# SX126xMB2xAS_e588v01a.net
KiCad netlist of a schematic drawn in Altium Designer
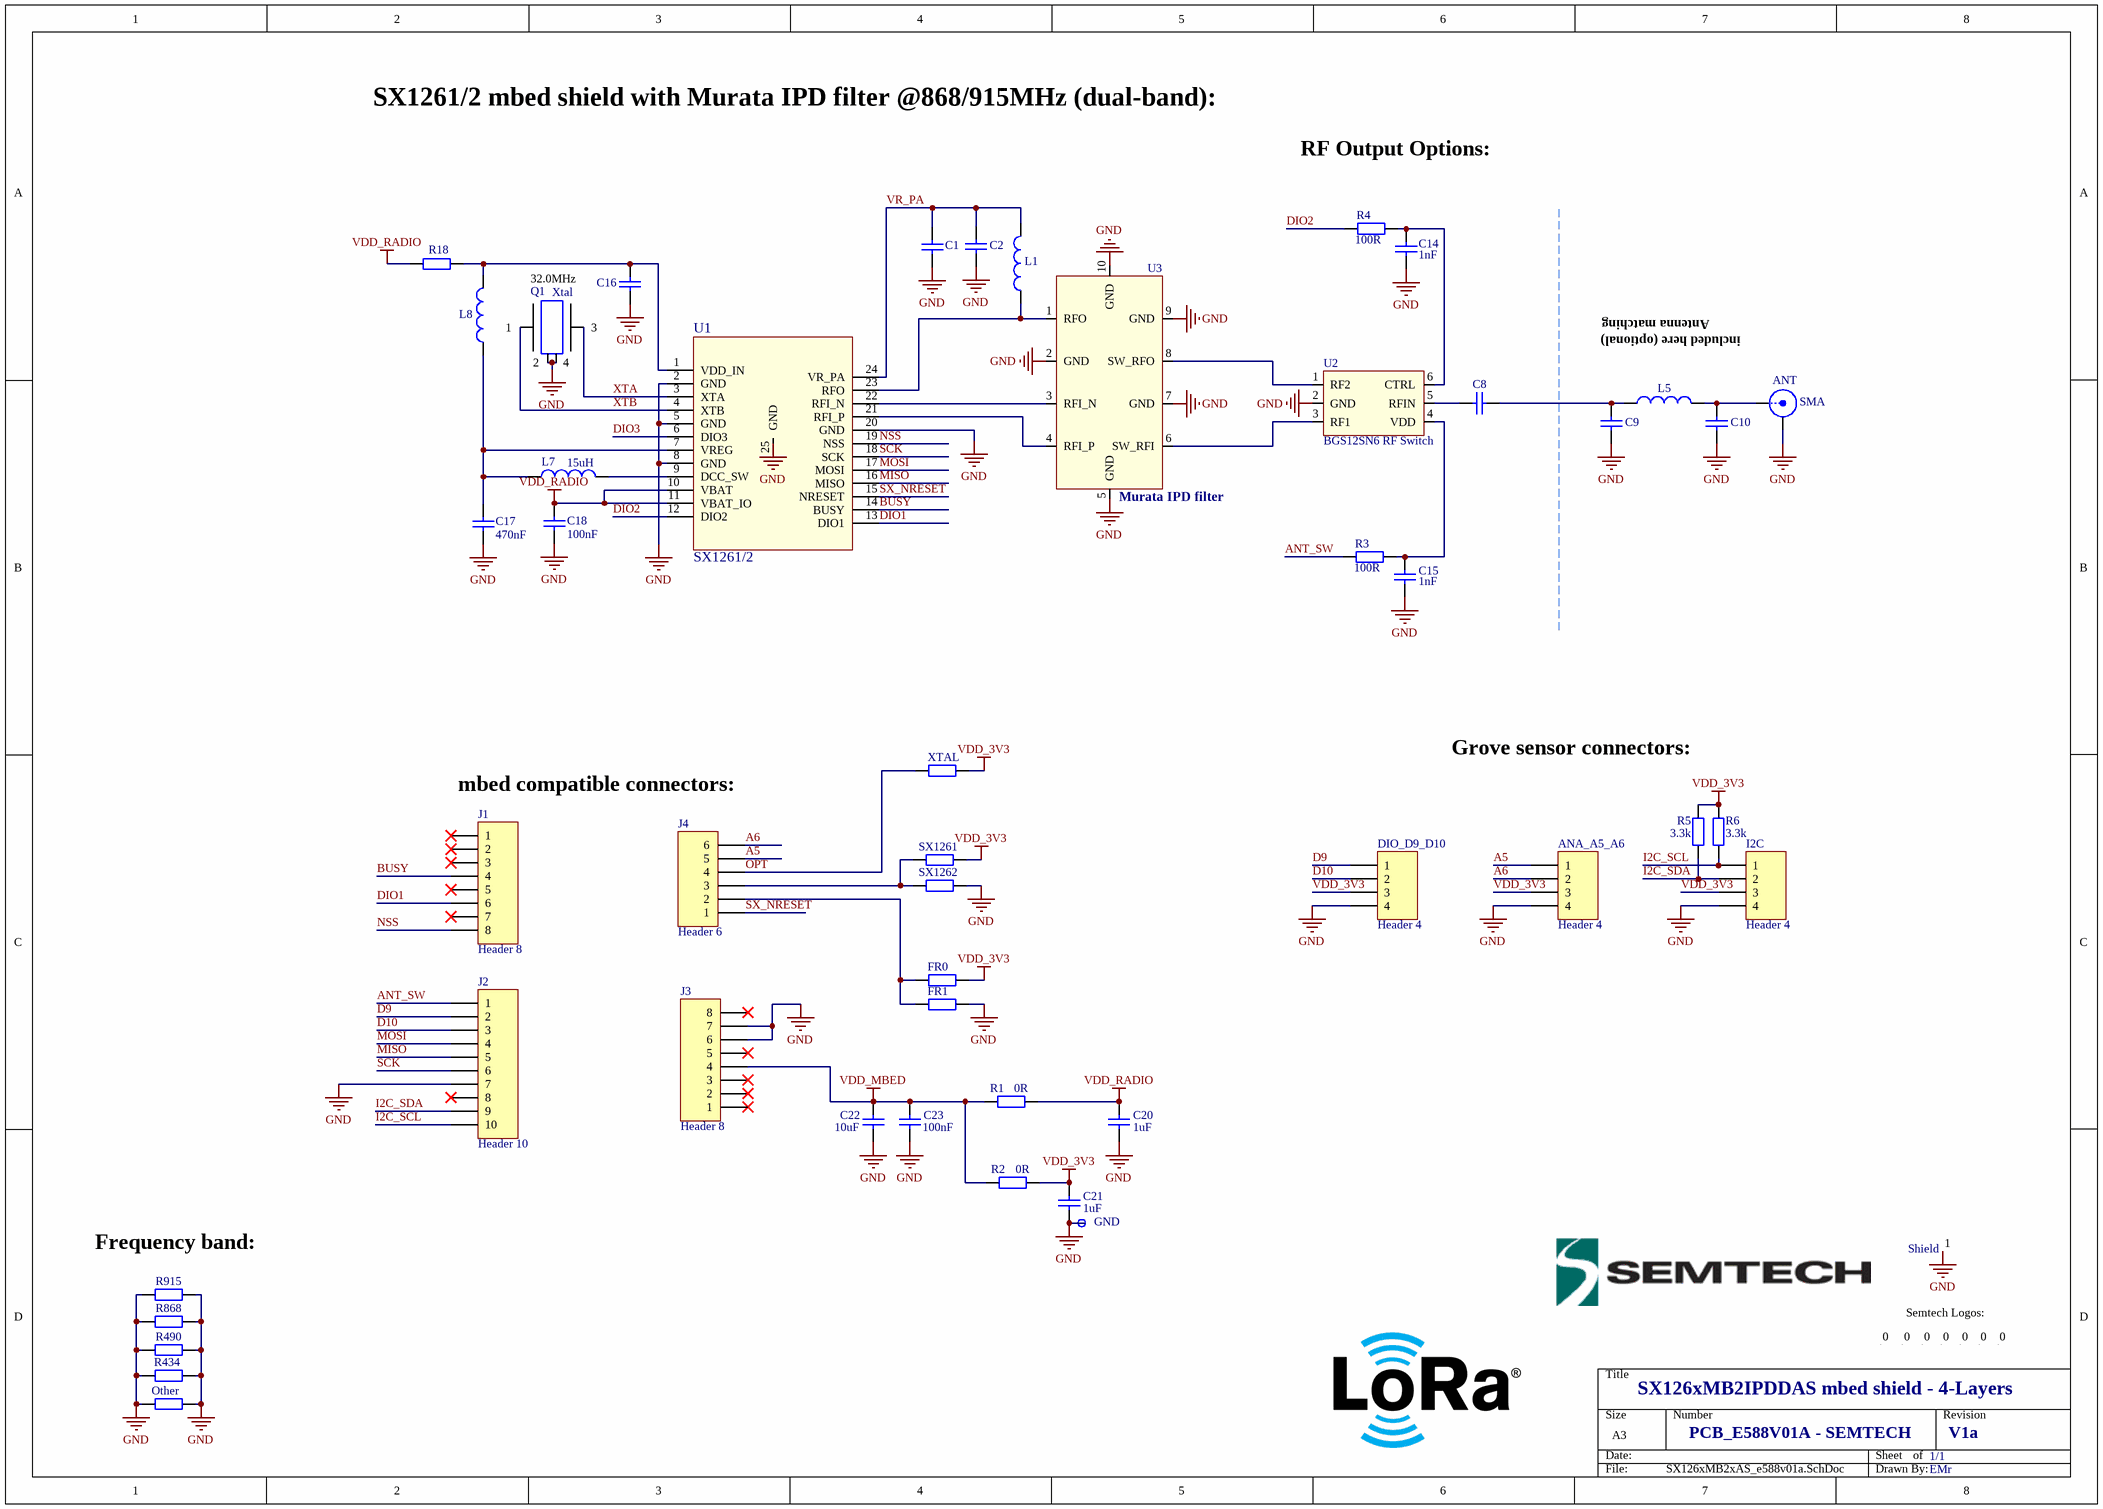
[diagram p0: SX126xMB2xAS_e588v01a.SchDoc]

(export (version "E")
  (design (tool "Eeschema 10.0.6"))
  (components
    (comp (ref "ANA_A5_A6")
      (value "Header 4")
      (footprint "1125S-4P_connector")
      (description "Header, 4-Pin")
      (fields (field (name "PUBLISHER") "Altium Limited"))
      (libsource (lib "SX126xMB2xAS_e588v01a") (part "Header 4"))
    )
    (comp (ref "ANT")
      (value "SMA")
      (footprint "SMA_end_launch_1.0mm_9.52mm")
      (description "SMA Straight Connector")
      (fields (field (name "PUBLISHER") "Altium Limited"))
      (libsource (lib "SX126xMB2xAS_e588v01a") (part "SMA"))
    )
    (comp (ref "C1")
      (value "Cap")
      (footprint "rlc_201_smd")
      (description "Capacitor SMD")
      (fields (field (name "PUBLISHER") "Altium Limited"))
      (libsource (lib "SX126xMB2xAS_e588v01a") (part "Cap"))
    )
    (comp (ref "C2")
      (value "Cap")
      (footprint "rlc_201_smd")
      (description "Capacitor SMD")
      (fields (field (name "PUBLISHER") "Altium Limited"))
      (libsource (lib "SX126xMB2xAS_e588v01a") (part "Cap"))
    )
    (comp (ref "C8")
      (value "Cap")
      (footprint "rlc_201_smd")
      (description "Capacitor SMD")
      (fields (field (name "PUBLISHER") "Altium Limited"))
      (libsource (lib "SX126xMB2xAS_e588v01a") (part "Cap"))
    )
    (comp (ref "C9")
      (value "Cap")
      (footprint "rlc_201_smd")
      (description "Capacitor SMD")
      (fields (field (name "PUBLISHER") "Altium Limited"))
      (libsource (lib "SX126xMB2xAS_e588v01a") (part "Cap"))
    )
    (comp (ref "C10")
      (value "Cap")
      (footprint "rlc_201_smd")
      (description "Capacitor SMD")
      (fields (field (name "PUBLISHER") "Altium Limited"))
      (libsource (lib "SX126xMB2xAS_e588v01a") (part "Cap"))
    )
    (comp (ref "C14")
      (value "1nF")
      (footprint "rlc_201_smd")
      (description "Capacitor SMD")
      (fields (field (name "Comment") "Cap") (field (name "PUBLISHER") "Altium Limited"))
      (libsource (lib "SX126xMB2xAS_e588v01a") (part "Cap"))
    )
    (comp (ref "C15")
      (value "1nF")
      (footprint "rlc_201_smd")
      (description "Capacitor SMD")
      (fields (field (name "Comment") "Cap") (field (name "PUBLISHER") "Altium Limited"))
      (libsource (lib "SX126xMB2xAS_e588v01a") (part "Cap"))
    )
    (comp (ref "C16")
      (value "Cap")
      (footprint "rlc_402_smd_small")
      (description "Capacitor SMD")
      (fields (field (name "PUBLISHER") "Altium Limited"))
      (libsource (lib "SX126xMB2xAS_e588v01a") (part "Cap"))
    )
    (comp (ref "C17")
      (value "470nF")
      (footprint "rlc_402_smd_small")
      (description "Capacitor SMD")
      (fields (field (name "Comment") "Cap") (field (name "PUBLISHER") "Altium Limited"))
      (libsource (lib "SX126xMB2xAS_e588v01a") (part "Cap"))
    )
    (comp (ref "C18")
      (value "100nF")
      (footprint "rlc_201_smd")
      (description "Capacitor SMD")
      (fields (field (name "Comment") "Cap") (field (name "PUBLISHER") "Altium Limited"))
      (libsource (lib "SX126xMB2xAS_e588v01a") (part "Cap"))
    )
    (comp (ref "C20")
      (value "1uF")
      (footprint "rlc_603_smd")
      (description "Capacitor SMD")
      (fields (field (name "Comment") "Cap") (field (name "PUBLISHER") "Altium Limited"))
      (libsource (lib "SX126xMB2xAS_e588v01a") (part "Cap"))
    )
    (comp (ref "C21")
      (value "1uF")
      (footprint "rlc_603_smd")
      (description "Capacitor SMD")
      (fields (field (name "Comment") "Cap") (field (name "PUBLISHER") "Altium Limited"))
      (libsource (lib "SX126xMB2xAS_e588v01a") (part "Cap"))
    )
    (comp (ref "C22")
      (value "10uF")
      (footprint "rlc_603_smd")
      (description "Capacitor SMD")
      (fields (field (name "Comment") "Cap") (field (name "PUBLISHER") "Altium Limited"))
      (libsource (lib "SX126xMB2xAS_e588v01a") (part "Cap"))
    )
    (comp (ref "C23")
      (value "100nF")
      (footprint "rlc_201_smd")
      (description "Capacitor SMD")
      (fields (field (name "Comment") "Cap") (field (name "PUBLISHER") "Altium Limited"))
      (libsource (lib "SX126xMB2xAS_e588v01a") (part "Cap"))
    )
    (comp (ref "DIO_D9_D10")
      (value "Header 4")
      (footprint "1125S-4P_connector")
      (description "Header, 4-Pin")
      (fields (field (name "PUBLISHER") "Altium Limited"))
      (libsource (lib "SX126xMB2xAS_e588v01a") (part "Header 4"))
    )
    (comp (ref "FR0")
      (value "Resistor")
      (footprint "rlc_402_smd")
      (description "Resistor SMD - IEC symbol version")
      (libsource (lib "") (part "Resistor_1"))
    )
    (comp (ref "FR1")
      (value "Resistor")
      (footprint "rlc_402_smd")
      (description "Resistor SMD - IEC symbol version")
      (libsource (lib "") (part "Resistor_1"))
    )
    (comp (ref "GND")
      (value "Test Pin")
      (footprint "pin_0.9mm")
      (libsource (lib "SX126xMB2xAS_e588v01a") (part "test_pin"))
    )
    (comp (ref "I2C")
      (value "Header 4")
      (footprint "1125S-4P_connector")
      (description "Header, 4-Pin")
      (fields (field (name "PUBLISHER") "Altium Limited"))
      (libsource (lib "SX126xMB2xAS_e588v01a") (part "Header 4"))
    )
    (comp (ref "J1")
      (value "Header 8")
      (footprint "HDR1X8")
      (description "Header, 8-Pin")
      (fields (field (name "PUBLISHER") "Altium Limited"))
      (libsource (lib "SX126xMB2xAS_e588v01a") (part "Header 8"))
    )
    (comp (ref "J2")
      (value "Header 10")
      (footprint "HDR1X10")
      (description "Header, 10-Pin")
      (fields (field (name "PUBLISHER") "Altium Limited"))
      (libsource (lib "SX126xMB2xAS_e588v01a") (part "Header 10"))
    )
    (comp (ref "J3")
      (value "Header 8")
      (footprint "HDR1X8")
      (description "Header, 8-Pin")
      (fields (field (name "PUBLISHER") "Altium Limited"))
      (libsource (lib "") (part "Header 8_1"))
    )
    (comp (ref "J4")
      (value "Header 6")
      (footprint "HDR1X6")
      (description "Header, 6-Pin")
      (fields (field (name "PUBLISHER") "Altium Limited"))
      (libsource (lib "SX126xMB2xAS_e588v01a") (part "Header 6"))
    )
    (comp (ref "L1")
      (value "Inductor")
      (footprint "rlc_402_smd_small")
      (description "Inductor SMD")
      (fields (field (name "PUBLISHER") "Altium Limited"))
      (libsource (lib "") (part "Inductor_1"))
    )
    (comp (ref "L5")
      (value "Inductor")
      (footprint "rlc_201_smd")
      (description "Inductor SMD")
      (fields (field (name "PUBLISHER") "Altium Limited"))
      (libsource (lib "") (part "Inductor_1"))
    )
    (comp (ref "L7")
      (value "15uH")
      (footprint "rlc_805_smd_small")
      (description "Inductor SMD")
      (fields (field (name "Comment") "Inductor") (field (name "PUBLISHER") "Altium Limited"))
      (libsource (lib "") (part "Inductor_1"))
    )
    (comp (ref "L8")
      (value "Inductor")
      (footprint "rlc_402_smd_small")
      (description "Inductor SMD")
      (fields (field (name "PUBLISHER") "Altium Limited"))
      (libsource (lib "SX126xMB2xAS_e588v01a") (part "Inductor"))
    )
    (comp (ref "Logo Bot1")
      (value "Logo symbol")
      (footprint "Logo LoRa Size4")
      (description "Schematic symbol for Logo")
      (libsource (lib "SX126xMB2xAS_e588v01a") (part "Logo"))
    )
    (comp (ref "Logo ESD1")
      (value "Logo symbol")
      (footprint "Logo ESD")
      (description "Schematic symbol for Logo")
      (libsource (lib "SX126xMB2xAS_e588v01a") (part "Logo"))
    )
    (comp (ref "Logo Recycling1")
      (value "Logo symbol")
      (footprint "Logo Recycling1")
      (description "Schematic symbol for Logo")
      (libsource (lib "SX126xMB2xAS_e588v01a") (part "Logo"))
    )
    (comp (ref "Logo Semtech_1")
      (value "Logo symbol")
      (footprint "logo_semtech_horiz_size3")
      (description "Schematic symbol for Logo")
      (libsource (lib "SX126xMB2xAS_e588v01a") (part "Logo"))
    )
    (comp (ref "Logo_LoRA_Top1")
      (value "Logo symbol")
      (footprint "Logo LoRa Size4")
      (description "Schematic symbol for Logo")
      (libsource (lib "SX126xMB2xAS_e588v01a") (part "Logo"))
    )
    (comp (ref "Logo_mbed1")
      (value "Logo symbol")
      (footprint "logo mbed 2")
      (description "Schematic symbol for Logo")
      (libsource (lib "SX126xMB2xAS_e588v01a") (part "Logo"))
    )
    (comp (ref "Logo_Semtech1")
      (value "Logo symbol")
      (footprint "logo_semtech_horiz_size4")
      (description "Schematic symbol for Logo")
      (libsource (lib "SX126xMB2xAS_e588v01a") (part "Logo"))
    )
    (comp (ref "Other")
      (value "Resistor")
      (footprint "rlc_402_smd")
      (description "Resistor SMD - IEC symbol version")
      (libsource (lib "SX126xMB2xAS_e588v01a") (part "Resistor"))
    )
    (comp (ref "Q1")
      (value "Xtal")
      (footprint "nd2016da")
      (description "Crystal with GND pins")
      (fields (field (name "ALTIUM_VALUE") "32.0MHz"))
      (libsource (lib "SX126xMB2xAS_e588v01a") (part "Xtal GND"))
    )
    (comp (ref "R1")
      (value "0R")
      (footprint "rlc_603_smd")
      (description "Resistor SMD - IEC symbol version")
      (fields (field (name "Comment") "Resistor"))
      (libsource (lib "SX126xMB2xAS_e588v01a") (part "Resistor"))
    )
    (comp (ref "R2")
      (value "0R")
      (footprint "rlc_603_smd")
      (description "Resistor SMD - IEC symbol version")
      (fields (field (name "Comment") "Resistor"))
      (libsource (lib "SX126xMB2xAS_e588v01a") (part "Resistor"))
    )
    (comp (ref "R3")
      (value "100R")
      (footprint "rlc_201_smd")
      (description "Resistor SMD - IEC symbol version")
      (fields (field (name "Comment") "Resistor"))
      (libsource (lib "SX126xMB2xAS_e588v01a") (part "Resistor"))
    )
    (comp (ref "R4")
      (value "100R")
      (footprint "rlc_201_smd")
      (description "Resistor SMD - IEC symbol version")
      (fields (field (name "Comment") "Resistor"))
      (libsource (lib "SX126xMB2xAS_e588v01a") (part "Resistor"))
    )
    (comp (ref "R5")
      (value "3.3k")
      (footprint "rlc_201_smd")
      (description "Resistor SMD - IEC symbol version")
      (fields (field (name "Comment") "Resistor"))
      (libsource (lib "") (part "Resistor_2"))
    )
    (comp (ref "R6")
      (value "3.3k")
      (footprint "rlc_201_smd")
      (description "Resistor SMD - IEC symbol version")
      (fields (field (name "Comment") "Resistor"))
      (libsource (lib "") (part "Resistor_2"))
    )
    (comp (ref "R18")
      (value "Resistor")
      (footprint "rlc_402_smd_small")
      (description "Resistor SMD - IEC symbol version")
      (libsource (lib "SX126xMB2xAS_e588v01a") (part "Resistor"))
    )
    (comp (ref "R434")
      (value "Resistor")
      (footprint "rlc_402_smd")
      (description "Resistor SMD - IEC symbol version")
      (libsource (lib "SX126xMB2xAS_e588v01a") (part "Resistor"))
    )
    (comp (ref "R490")
      (value "Resistor")
      (footprint "rlc_402_smd")
      (description "Resistor SMD - IEC symbol version")
      (libsource (lib "SX126xMB2xAS_e588v01a") (part "Resistor"))
    )
    (comp (ref "R868")
      (value "Resistor")
      (footprint "rlc_402_smd")
      (description "Resistor SMD - IEC symbol version")
      (libsource (lib "SX126xMB2xAS_e588v01a") (part "Resistor"))
    )
    (comp (ref "R915")
      (value "Resistor")
      (footprint "rlc_402_smd")
      (description "Resistor SMD - IEC symbol version")
      (libsource (lib "SX126xMB2xAS_e588v01a") (part "Resistor"))
    )
    (comp (ref "Shield")
      (value "Logo symbol")
      (footprint "BMIS-209-F - Shield")
      (description "Shield - EMI Gasket - Standard Surface Mount Shields")
      (libsource (lib "SX126xMB2xAS_e588v01a") (part "Shield"))
    )
    (comp (ref "SX1261")
      (value "Resistor")
      (footprint "rlc_402_smd")
      (description "Resistor SMD - IEC symbol version")
      (libsource (lib "") (part "Resistor_1"))
    )
    (comp (ref "SX1262")
      (value "Resistor")
      (footprint "rlc_402_smd")
      (description "Resistor SMD - IEC symbol version")
      (libsource (lib "") (part "Resistor_1"))
    )
    (comp (ref "U1")
      (value "SX1261/2")
      (footprint "vqfn24_4x4mm")
      (description "SX1262- Ultra low power RF transceiver")
      (libsource (lib "SX126xMB2xAS_e588v01a") (part "SX126x"))
    )
    (comp (ref "U2")
      (value "BGS12SN6 RF Switch")
      (footprint "TSNP-6-2")
      (description "BGS12SN6 Infineon RF Switch")
      (libsource (lib "SX126xMB2xAS_e588v01a") (part "BGS12SN6 RF Switch"))
    )
    (comp (ref "U3")
      (value "Murata IPD filter")
      (footprint "IPD Filter")
      (description "0900FM15D0039 - Johanson IPD Filter for SX1261, SX1262")
      (libsource (lib "SX126xMB2xAS_e588v01a") (part "IPD filter"))
    )
    (comp (ref "XTAL")
      (value "Resistor")
      (footprint "rlc_402_smd")
      (description "Resistor SMD - IEC symbol version")
      (libsource (lib "") (part "Resistor_1"))
    )
  )
  (nets
    (net (code "1") (name "/A5") (class "Default")
      (node (ref "ANA_A5_A6") (pin "1") (pinfunction "1_1") (pintype "passive"))
      (node (ref "J4") (pin "5") (pinfunction "5_5") (pintype "passive"))
    )
    (net (code "2") (name "/A6") (class "Default")
      (node (ref "ANA_A5_A6") (pin "2") (pinfunction "2_2") (pintype "passive"))
      (node (ref "J4") (pin "6") (pinfunction "6_6") (pintype "passive"))
    )
    (net (code "3") (name "/ANT_SW") (class "Default")
      (node (ref "J2") (pin "1") (pinfunction "1_1") (pintype "passive"))
      (node (ref "R3") (pin "2") (pinfunction "2_2") (pintype "passive"))
    )
    (net (code "4") (name "/BUSY") (class "Default")
      (node (ref "J1") (pin "4") (pinfunction "4_4") (pintype "passive"))
      (node (ref "U1") (pin "14") (pinfunction "BUSY_14") (pintype "passive"))
    )
    (net (code "5") (name "/D9") (class "Default")
      (node (ref "DIO_D9_D10") (pin "1") (pinfunction "1_1") (pintype "passive"))
      (node (ref "J2") (pin "2") (pinfunction "2_2") (pintype "passive"))
    )
    (net (code "6") (name "/D10") (class "Default")
      (node (ref "DIO_D9_D10") (pin "2") (pinfunction "2_2") (pintype "passive"))
      (node (ref "J2") (pin "3") (pinfunction "3_3") (pintype "passive"))
    )
    (net (code "7") (name "/DIO1") (class "Default")
      (node (ref "J1") (pin "6") (pinfunction "6_6") (pintype "passive"))
      (node (ref "U1") (pin "13") (pinfunction "DIO1_13") (pintype "passive"))
    )
    (net (code "8") (name "/DIO2") (class "Default")
      (node (ref "R4") (pin "2") (pinfunction "2_2") (pintype "passive"))
      (node (ref "U1") (pin "12") (pinfunction "DIO2_12") (pintype "passive"))
    )
    (net (code "9") (name "/DIO3") (class "Default")
      (node (ref "U1") (pin "6") (pinfunction "DIO3_6") (pintype "passive"))
    )
    (net (code "10") (name "/I2C_SCL") (class "Default")
      (node (ref "I2C") (pin "1") (pinfunction "1_1") (pintype "passive"))
      (node (ref "J2") (pin "10") (pinfunction "10_10") (pintype "passive"))
      (node (ref "R6") (pin "1") (pinfunction "1_1") (pintype "passive"))
    )
    (net (code "11") (name "/I2C_SDA") (class "Default")
      (node (ref "I2C") (pin "2") (pinfunction "2_2") (pintype "passive"))
      (node (ref "J2") (pin "9") (pinfunction "9_9") (pintype "passive"))
      (node (ref "R5") (pin "1") (pinfunction "1_1") (pintype "passive"))
    )
    (net (code "12") (name "/MISO") (class "Default")
      (node (ref "J2") (pin "5") (pinfunction "5_5") (pintype "passive"))
      (node (ref "U1") (pin "16") (pinfunction "MISO_16") (pintype "passive"))
    )
    (net (code "13") (name "/MOSI") (class "Default")
      (node (ref "J2") (pin "4") (pinfunction "4_4") (pintype "passive"))
      (node (ref "U1") (pin "17") (pinfunction "MOSI_17") (pintype "passive"))
    )
    (net (code "14") (name "/NSS") (class "Default")
      (node (ref "J1") (pin "8") (pinfunction "8_8") (pintype "passive"))
      (node (ref "U1") (pin "19") (pinfunction "NSS_19") (pintype "passive"))
    )
    (net (code "15") (name "/OPT") (class "Default")
      (node (ref "J4") (pin "4") (pinfunction "4_4") (pintype "passive"))
      (node (ref "XTAL") (pin "2") (pinfunction "2_2") (pintype "passive"))
    )
    (net (code "16") (name "/SCK") (class "Default")
      (node (ref "J2") (pin "6") (pinfunction "6_6") (pintype "passive"))
      (node (ref "U1") (pin "18") (pinfunction "SCK_18") (pintype "passive"))
    )
    (net (code "17") (name "/SX_NRESET") (class "Default")
      (node (ref "J4") (pin "1") (pinfunction "1_1") (pintype "passive"))
      (node (ref "U1") (pin "15") (pinfunction "NRESET_15") (pintype "passive"))
    )
    (net (code "18") (name "/VR_PA") (class "Default")
      (node (ref "C1") (pin "2") (pinfunction "2_2") (pintype "passive"))
      (node (ref "C2") (pin "2") (pinfunction "2_2") (pintype "passive"))
      (node (ref "L1") (pin "2") (pinfunction "2_2") (pintype "passive"))
      (node (ref "U1") (pin "24") (pinfunction "VR_PA_24") (pintype "power_in"))
    )
    (net (code "19") (name "/XTA") (class "Default")
      (node (ref "Q1") (pin "3") (pinfunction "3_3") (pintype "passive"))
      (node (ref "U1") (pin "3") (pinfunction "XTA_3") (pintype "passive"))
    )
    (net (code "20") (name "/XTB") (class "Default")
      (node (ref "Q1") (pin "1") (pinfunction "1_1") (pintype "passive"))
      (node (ref "U1") (pin "4") (pinfunction "XTB_4") (pintype "passive"))
    )
    (net (code "21") (name "GND") (class "Default")
      (node (ref "ANA_A5_A6") (pin "4") (pinfunction "4_4") (pintype "passive"))
      (node (ref "ANT") (pin "2") (pinfunction "GND_2") (pintype "passive"))
      (node (ref "C1") (pin "1") (pinfunction "1_1") (pintype "passive"))
      (node (ref "C10") (pin "1") (pinfunction "1_1") (pintype "passive"))
      (node (ref "C14") (pin "2") (pinfunction "2_2") (pintype "passive"))
      (node (ref "C15") (pin "2") (pinfunction "2_2") (pintype "passive"))
      (node (ref "C16") (pin "1") (pinfunction "1_1") (pintype "passive"))
      (node (ref "C17") (pin "1") (pinfunction "1_1") (pintype "passive"))
      (node (ref "C18") (pin "1") (pinfunction "1_1") (pintype "passive"))
      (node (ref "C2") (pin "1") (pinfunction "1_1") (pintype "passive"))
      (node (ref "C20") (pin "1") (pinfunction "1_1") (pintype "passive"))
      (node (ref "C21") (pin "1") (pinfunction "1_1") (pintype "passive"))
      (node (ref "C22") (pin "1") (pinfunction "1_1") (pintype "passive"))
      (node (ref "C23") (pin "1") (pinfunction "1_1") (pintype "passive"))
      (node (ref "C9") (pin "1") (pinfunction "1_1") (pintype "passive"))
      (node (ref "DIO_D9_D10") (pin "4") (pinfunction "4_4") (pintype "passive"))
      (node (ref "FR1") (pin "1") (pinfunction "1_1") (pintype "passive"))
      (node (ref "GND") (pin "1") (pinfunction "pin_1") (pintype "passive"))
      (node (ref "I2C") (pin "4") (pinfunction "4_4") (pintype "passive"))
      (node (ref "J2") (pin "7") (pinfunction "7_7") (pintype "passive"))
      (node (ref "J3") (pin "6") (pinfunction "6_6") (pintype "passive"))
      (node (ref "J3") (pin "7") (pinfunction "7_7") (pintype "passive"))
      (node (ref "Other") (pin "1") (pinfunction "1_1") (pintype "passive"))
      (node (ref "Other") (pin "2") (pinfunction "2_2") (pintype "passive"))
      (node (ref "Q1") (pin "2") (pinfunction "2_2") (pintype "passive"))
      (node (ref "Q1") (pin "4") (pinfunction "4_4") (pintype "passive"))
      (node (ref "R434") (pin "1") (pinfunction "1_1") (pintype "passive"))
      (node (ref "R434") (pin "2") (pinfunction "2_2") (pintype "passive"))
      (node (ref "R490") (pin "1") (pinfunction "1_1") (pintype "passive"))
      (node (ref "R490") (pin "2") (pinfunction "2_2") (pintype "passive"))
      (node (ref "R868") (pin "1") (pinfunction "1_1") (pintype "passive"))
      (node (ref "R868") (pin "2") (pinfunction "2_2") (pintype "passive"))
      (node (ref "R915") (pin "1") (pinfunction "1_1") (pintype "passive"))
      (node (ref "R915") (pin "2") (pinfunction "2_2") (pintype "passive"))
      (node (ref "SX1262") (pin "1") (pinfunction "1_1") (pintype "passive"))
      (node (ref "Shield") (pin "1") (pinfunction "1_1") (pintype "passive"))
      (node (ref "U1") (pin "2") (pinfunction "GND_2") (pintype "passive"))
      (node (ref "U1") (pin "20") (pinfunction "GND_20") (pintype "passive"))
      (node (ref "U1") (pin "25") (pinfunction "GND_25") (pintype "passive"))
      (node (ref "U1") (pin "5") (pinfunction "GND_5") (pintype "passive"))
      (node (ref "U1") (pin "8") (pinfunction "GND_8") (pintype "passive"))
      (node (ref "U2") (pin "2") (pinfunction "GND_2") (pintype "passive"))
      (node (ref "U3") (pin "10") (pinfunction "GND_10") (pintype "power_in"))
      (node (ref "U3") (pin "2") (pinfunction "GND_2") (pintype "power_in"))
      (node (ref "U3") (pin "5") (pinfunction "GND_5") (pintype "power_in"))
      (node (ref "U3") (pin "7") (pinfunction "GND_7") (pintype "power_in"))
      (node (ref "U3") (pin "9") (pinfunction "GND_9") (pintype "power_in"))
    )
    (net (code "22") (name "Net-(ANT-Signal)") (class "Default")
      (node (ref "ANT") (pin "1") (pinfunction "Signal_1") (pintype "passive"))
      (node (ref "C10") (pin "2") (pinfunction "2_2") (pintype "passive"))
      (node (ref "L5") (pin "2") (pinfunction "2_2") (pintype "passive"))
    )
    (net (code "23") (name "Net-(C8-Pad1)") (class "Default")
      (node (ref "C8") (pin "1") (pinfunction "1_1") (pintype "passive"))
      (node (ref "C9") (pin "2") (pinfunction "2_2") (pintype "passive"))
      (node (ref "L5") (pin "1") (pinfunction "1_1") (pintype "passive"))
    )
    (net (code "24") (name "Net-(FR0-Pad2)") (class "Default")
      (node (ref "FR0") (pin "2") (pinfunction "2_2") (pintype "passive"))
      (node (ref "FR1") (pin "2") (pinfunction "2_2") (pintype "passive"))
      (node (ref "J4") (pin "2") (pinfunction "2_2") (pintype "passive"))
    )
    (net (code "25") (name "Net-(J4-Pad3)") (class "Default")
      (node (ref "J4") (pin "3") (pinfunction "3_3") (pintype "passive"))
      (node (ref "SX1261") (pin "2") (pinfunction "2_2") (pintype "passive"))
      (node (ref "SX1262") (pin "2") (pinfunction "2_2") (pintype "passive"))
    )
    (net (code "26") (name "Net-(U1-DCC_SW)") (class "Default")
      (node (ref "L7") (pin "2") (pinfunction "2_2") (pintype "passive"))
      (node (ref "U1") (pin "9") (pinfunction "DCC_SW_9") (pintype "power_in"))
    )
    (net (code "27") (name "Net-(U1-RFI_N)") (class "Default")
      (node (ref "U1") (pin "22") (pinfunction "RFI_N_22") (pintype "passive"))
      (node (ref "U3") (pin "3") (pinfunction "RFI_N_3") (pintype "passive"))
    )
    (net (code "28") (name "Net-(U1-RFI_P)") (class "Default")
      (node (ref "U1") (pin "21") (pinfunction "RFI_P_21") (pintype "passive"))
      (node (ref "U3") (pin "4") (pinfunction "RFI_P_4") (pintype "passive"))
    )
    (net (code "29") (name "Net-(U1-RFO)") (class "Default")
      (node (ref "L1") (pin "1") (pinfunction "1_1") (pintype "passive"))
      (node (ref "U1") (pin "23") (pinfunction "RFO_23") (pintype "passive"))
      (node (ref "U3") (pin "1") (pinfunction "RFO_1") (pintype "passive"))
    )
    (net (code "30") (name "Net-(U1-VDD_IN)") (class "Default")
      (node (ref "C16") (pin "2") (pinfunction "2_2") (pintype "passive"))
      (node (ref "L8") (pin "1") (pinfunction "1_1") (pintype "passive"))
      (node (ref "R18") (pin "1") (pinfunction "1_1") (pintype "passive"))
      (node (ref "U1") (pin "1") (pinfunction "VDD_IN_1") (pintype "power_in"))
    )
    (net (code "31") (name "Net-(U1-VREG)") (class "Default")
      (node (ref "C17") (pin "2") (pinfunction "2_2") (pintype "passive"))
      (node (ref "L7") (pin "1") (pinfunction "1_1") (pintype "passive"))
      (node (ref "L8") (pin "2") (pinfunction "2_2") (pintype "passive"))
      (node (ref "U1") (pin "7") (pinfunction "VREG_7") (pintype "power_in"))
    )
    (net (code "32") (name "Net-(U2-CTRL)") (class "Default")
      (node (ref "C14") (pin "1") (pinfunction "1_1") (pintype "passive"))
      (node (ref "R4") (pin "1") (pinfunction "1_1") (pintype "passive"))
      (node (ref "U2") (pin "6") (pinfunction "CTRL_6") (pintype "passive"))
    )
    (net (code "33") (name "Net-(U2-RF1)") (class "Default")
      (node (ref "U2") (pin "3") (pinfunction "RF1_3") (pintype "passive"))
      (node (ref "U3") (pin "6") (pinfunction "SW_RFI_6") (pintype "passive"))
    )
    (net (code "34") (name "Net-(U2-RF2)") (class "Default")
      (node (ref "U2") (pin "1") (pinfunction "RF2_1") (pintype "passive"))
      (node (ref "U3") (pin "8") (pinfunction "SW_RFO_8") (pintype "passive"))
    )
    (net (code "35") (name "Net-(U2-RFIN)") (class "Default")
      (node (ref "C8") (pin "2") (pinfunction "2_2") (pintype "passive"))
      (node (ref "U2") (pin "5") (pinfunction "RFIN_5") (pintype "passive"))
    )
    (net (code "36") (name "Net-(U2-VDD)") (class "Default")
      (node (ref "C15") (pin "1") (pinfunction "1_1") (pintype "passive"))
      (node (ref "R3") (pin "1") (pinfunction "1_1") (pintype "passive"))
      (node (ref "U2") (pin "4") (pinfunction "VDD_4") (pintype "power_in"))
    )
    (net (code "37") (name "VDD_3V3") (class "Default")
      (node (ref "ANA_A5_A6") (pin "3") (pinfunction "3_3") (pintype "passive"))
      (node (ref "C21") (pin "2") (pinfunction "2_2") (pintype "passive"))
      (node (ref "DIO_D9_D10") (pin "3") (pinfunction "3_3") (pintype "passive"))
      (node (ref "FR0") (pin "1") (pinfunction "1_1") (pintype "passive"))
      (node (ref "I2C") (pin "3") (pinfunction "3_3") (pintype "passive"))
      (node (ref "R2") (pin "1") (pinfunction "1_1") (pintype "passive"))
      (node (ref "R5") (pin "2") (pinfunction "2_2") (pintype "passive"))
      (node (ref "R6") (pin "2") (pinfunction "2_2") (pintype "passive"))
      (node (ref "SX1261") (pin "1") (pinfunction "1_1") (pintype "passive"))
      (node (ref "XTAL") (pin "1") (pinfunction "1_1") (pintype "passive"))
    )
    (net (code "38") (name "VDD_MBED") (class "Default")
      (node (ref "C22") (pin "2") (pinfunction "2_2") (pintype "passive"))
      (node (ref "C23") (pin "2") (pinfunction "2_2") (pintype "passive"))
      (node (ref "J3") (pin "4") (pinfunction "4_4") (pintype "passive"))
      (node (ref "R1") (pin "2") (pinfunction "2_2") (pintype "passive"))
      (node (ref "R2") (pin "2") (pinfunction "2_2") (pintype "passive"))
    )
    (net (code "39") (name "VDD_RADIO") (class "Default")
      (node (ref "C18") (pin "2") (pinfunction "2_2") (pintype "passive"))
      (node (ref "C20") (pin "2") (pinfunction "2_2") (pintype "passive"))
      (node (ref "R1") (pin "1") (pinfunction "1_1") (pintype "passive"))
      (node (ref "R18") (pin "2") (pinfunction "2_2") (pintype "passive"))
      (node (ref "U1") (pin "10") (pinfunction "VBAT_10") (pintype "power_in"))
      (node (ref "U1") (pin "11") (pinfunction "VBAT_IO_11") (pintype "power_in"))
    )
    (net (code "40") (name "unconnected-(J1-Pad1)") (class "Default")
      (node (ref "J1") (pin "1") (pinfunction "1_1") (pintype "passive+no_connect"))
    )
    (net (code "41") (name "unconnected-(J1-Pad2)") (class "Default")
      (node (ref "J1") (pin "2") (pinfunction "2_2") (pintype "passive+no_connect"))
    )
    (net (code "42") (name "unconnected-(J1-Pad3)") (class "Default")
      (node (ref "J1") (pin "3") (pinfunction "3_3") (pintype "passive+no_connect"))
    )
    (net (code "43") (name "unconnected-(J1-Pad5)") (class "Default")
      (node (ref "J1") (pin "5") (pinfunction "5_5") (pintype "passive+no_connect"))
    )
    (net (code "44") (name "unconnected-(J1-Pad7)") (class "Default")
      (node (ref "J1") (pin "7") (pinfunction "7_7") (pintype "passive+no_connect"))
    )
    (net (code "45") (name "unconnected-(J2-Pad8)") (class "Default")
      (node (ref "J2") (pin "8") (pinfunction "8_8") (pintype "passive+no_connect"))
    )
    (net (code "46") (name "unconnected-(J3-Pad1)") (class "Default")
      (node (ref "J3") (pin "1") (pinfunction "1_1") (pintype "passive+no_connect"))
    )
    (net (code "47") (name "unconnected-(J3-Pad2)") (class "Default")
      (node (ref "J3") (pin "2") (pinfunction "2_2") (pintype "passive+no_connect"))
    )
    (net (code "48") (name "unconnected-(J3-Pad3)") (class "Default")
      (node (ref "J3") (pin "3") (pinfunction "3_3") (pintype "passive+no_connect"))
    )
    (net (code "49") (name "unconnected-(J3-Pad5)") (class "Default")
      (node (ref "J3") (pin "5") (pinfunction "5_5") (pintype "passive+no_connect"))
    )
    (net (code "50") (name "unconnected-(J3-Pad8)") (class "Default")
      (node (ref "J3") (pin "8") (pinfunction "8_8") (pintype "passive+no_connect"))
    )
    (net (code "51") (name "unconnected-(Logo Bot1-Pad0)") (class "Default")
      (node (ref "Logo Bot1") (pin "0") (pinfunction "0_0") (pintype "passive"))
    )
    (net (code "52") (name "unconnected-(Logo ESD1-Pad0)") (class "Default")
      (node (ref "Logo ESD1") (pin "0") (pinfunction "0_0") (pintype "passive"))
    )
    (net (code "53") (name "unconnected-(Logo Recycling1-Pad0)") (class "Default")
      (node (ref "Logo Recycling1") (pin "0") (pinfunction "0_0") (pintype "passive"))
    )
    (net (code "54") (name "unconnected-(Logo Semtech_1-Pad0)") (class "Default")
      (node (ref "Logo Semtech_1") (pin "0") (pinfunction "0_0") (pintype "passive"))
    )
    (net (code "55") (name "unconnected-(Logo_LoRA_Top1-Pad0)") (class "Default")
      (node (ref "Logo_LoRA_Top1") (pin "0") (pinfunction "0_0") (pintype "passive"))
    )
    (net (code "56") (name "unconnected-(Logo_Semtech1-Pad0)") (class "Default")
      (node (ref "Logo_Semtech1") (pin "0") (pinfunction "0_0") (pintype "passive"))
    )
    (net (code "57") (name "unconnected-(Logo_mbed1-Pad0)") (class "Default")
      (node (ref "Logo_mbed1") (pin "0") (pinfunction "0_0") (pintype "passive"))
    )
  )
)
